# OZ440-SE100-CAR003_sheet15.net
KiCad netlist of a schematic drawn in Altium Designer
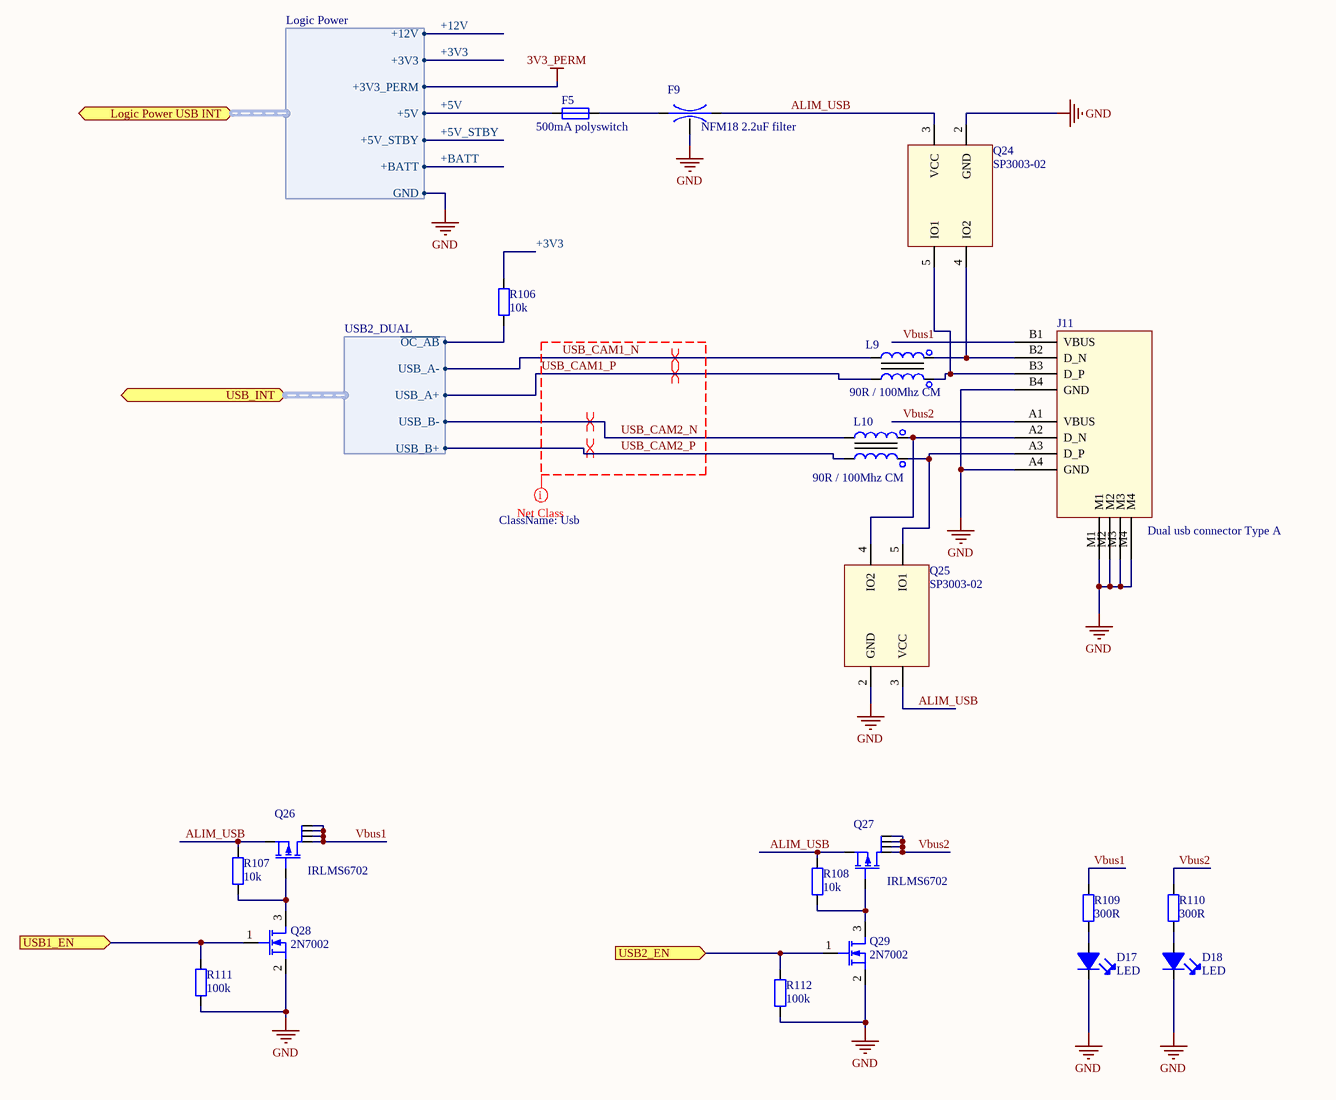
[diagram p0: OZ440-SE100-CAR003_sheet15.SchDoc]

(export (version "E")
  (design (tool "Eeschema 10.0.6"))
  (components
    (comp (ref "D17")
      (value "LED")
      (footprint "0603-SPE-LED")
      (description "SMD Green LED 0603")
      (fields (field (name "DISPLAYED REFERENCE") "LED") (field (name "MANUFACTURER") "KingBright"))
      (libsource (lib "lib_NAIO") (part "LED"))
    )
    (comp (ref "D18")
      (value "LED")
      (footprint "0603-SPE-LED")
      (description "SMD Green LED 0603")
      (fields (field (name "DISPLAYED REFERENCE") "LED") (field (name "MANUFACTURER") "KingBright"))
      (libsource (lib "lib_NAIO") (part "LED"))
    )
    (comp (ref "F5")
      (value "FUSE-SMD")
      (footprint "R0805-STD")
      (description "0805 500mA resettable fuse")
      (fields (field (name "DISPLAYED REFERENCE") "500mA polyswitch") (field (name "MANUFACTURER") "BOURNS"))
      (libsource (lib "lib_NAIO") (part "FUSE-SMD"))
    )
    (comp (ref "F9")
      (value "LC_FILTER-STD")
      (footprint "LC_0603-STD")
      (description "2A LC filter")
      (fields
        (field (name "DISPLAYED REFERENCE") "NFM18 2.2uF filter")
        (field (name "MANUFACTURER") "MURATA")
      )
      (libsource (lib "lib_NAIO") (part "LC_FILTER-STD"))
    )
    (comp (ref "J11")
      (value "CONN-STD_USB_A_DUAL")
      (footprint "CONN-STD-USB_A")
      (description "Dual USB Type A connector")
      (fields
        (field (name "DISPLAYED REFERENCE") "Dual usb connector Type A")
        (field (name "MANUFACTURER") "FCI")
      )
      (libsource (lib "lib_NAIO") (part "CONN-STD_USB_A_DUAL"))
    )
    (comp (ref "L9")
      (value "IND-MC-SMD")
      (footprint "L-SPE-0805_MC_EXC34")
      (description "USB common mode inductor")
      (fields
        (field (name "DISPLAYED REFERENCE") "90R / 100Mhz CM")
        (field (name "MANUFACTURER") "PANASONIC")
      )
      (libsource (lib "lib_NAIO") (part "IND-MC-SMD"))
    )
    (comp (ref "L10")
      (value "IND-MC-SMD")
      (footprint "L-SPE-0805_MC_EXC34")
      (description "USB common mode inductor")
      (fields
        (field (name "DISPLAYED REFERENCE") "90R / 100Mhz CM")
        (field (name "MANUFACTURER") "PANASONIC")
      )
      (libsource (lib "lib_NAIO") (part "IND-MC-SMD"))
    )
    (comp (ref "Q24")
      (value "SP03003_02-SC70")
      (footprint "SC70-SPE-SP3003")
      (description "Low capacitance ESD TVS")
      (fields (field (name "DISPLAYED REFERENCE") "SP3003-02") (field (name "MANUFACTURER") "LITTLEFUSE"))
      (libsource (lib "") (part "SP03003_02-SC70_1"))
    )
    (comp (ref "Q25")
      (value "SP03003_02-SC70")
      (footprint "SC70-SPE-SP3003")
      (description "Low capacitance ESD TVS")
      (fields (field (name "DISPLAYED REFERENCE") "SP3003-02") (field (name "MANUFACTURER") "LITTLEFUSE"))
      (libsource (lib "lib_NAIO") (part "SP03003_02-SC70"))
    )
    (comp (ref "Q26")
      (value "IRLMS6702-MICRO6")
      (footprint "MICRO6-SPE-IRLMS6702")
      (description "2A P channel MOSFET in MICRO6 package")
      (fields (field (name "DISPLAYED REFERENCE") "IRLMS6702") (field (name "MANUFACTURER") "IRF"))
      (libsource (lib "lib_NAIO") (part "IRLMS6702-MICRO6"))
    )
    (comp (ref "Q27")
      (value "IRLMS6702-MICRO6")
      (footprint "MICRO6-SPE-IRLMS6702")
      (description "2A P channel MOSFET in MICRO6 package")
      (fields (field (name "DISPLAYED REFERENCE") "IRLMS6702") (field (name "MANUFACTURER") "IRF"))
      (libsource (lib "lib_NAIO") (part "IRLMS6702-MICRO6"))
    )
    (comp (ref "Q28")
      (value "2N7002-SMD3P")
      (footprint "SOT23-SPE-2N7002")
      (description "N-Channel Enhancement Mode Field Effect Transistor")
      (fields (field (name "DISPLAYED REFERENCE") "2N7002") (field (name "MANUFACTURER") "FAIRCHILD"))
      (libsource (lib "lib_NAIO") (part "2N7002-SMD3P"))
    )
    (comp (ref "Q29")
      (value "2N7002-SMD3P")
      (footprint "SOT23-SPE-2N7002")
      (description "N-Channel Enhancement Mode Field Effect Transistor")
      (fields (field (name "DISPLAYED REFERENCE") "2N7002") (field (name "MANUFACTURER") "FAIRCHILD"))
      (libsource (lib "lib_NAIO") (part "2N7002-SMD3P"))
    )
    (comp (ref "R106")
      (value "RES-SMD")
      (footprint "R0805-STD")
      (description "10k Ohm 0805 SMD resistor")
      (fields
        (field (name "DISPLAYED REFERENCE") "10k")
        (field (name "TOLERANCE") "1 %")
        (field (name "MANUFACTURER") "Vishay")
      )
      (libsource (lib "lib_NAIO") (part "RES-SMD"))
    )
    (comp (ref "R107")
      (value "RES-SMD")
      (footprint "R0805-STD")
      (description "10k Ohm 0805 SMD resistor")
      (fields
        (field (name "DISPLAYED REFERENCE") "10k")
        (field (name "TOLERANCE") "1 %")
        (field (name "MANUFACTURER") "Vishay")
      )
      (libsource (lib "lib_NAIO") (part "RES-SMD"))
    )
    (comp (ref "R108")
      (value "RES-SMD")
      (footprint "R0805-STD")
      (description "10k Ohm 0805 SMD resistor")
      (fields
        (field (name "DISPLAYED REFERENCE") "10k")
        (field (name "TOLERANCE") "1 %")
        (field (name "MANUFACTURER") "Vishay")
      )
      (libsource (lib "lib_NAIO") (part "RES-SMD"))
    )
    (comp (ref "R109")
      (value "RES-SMD")
      (footprint "R0805-STD")
      (description "300 ohm 0805 SMD resistor")
      (fields
        (field (name "DISPLAYED REFERENCE") "300R")
        (field (name "TOLERANCE") "1%")
        (field (name "MANUFACTURER") "Vishay")
      )
      (libsource (lib "lib_NAIO") (part "RES-SMD"))
    )
    (comp (ref "R110")
      (value "RES-SMD")
      (footprint "R0805-STD")
      (description "300 ohm 0805 SMD resistor")
      (fields
        (field (name "DISPLAYED REFERENCE") "300R")
        (field (name "TOLERANCE") "1%")
        (field (name "MANUFACTURER") "Vishay")
      )
      (libsource (lib "lib_NAIO") (part "RES-SMD"))
    )
    (comp (ref "R111")
      (value "RES-SMD")
      (footprint "R0805-STD")
      (description "100k Ohm 0805 SMD resistor")
      (fields
        (field (name "DISPLAYED REFERENCE") "100k")
        (field (name "TOLERANCE") "1 %")
        (field (name "MANUFACTURER") "Vishay")
      )
      (libsource (lib "lib_NAIO") (part "RES-SMD"))
    )
    (comp (ref "R112")
      (value "RES-SMD")
      (footprint "R0805-STD")
      (description "100k Ohm 0805 SMD resistor")
      (fields
        (field (name "DISPLAYED REFERENCE") "100k")
        (field (name "TOLERANCE") "1 %")
        (field (name "MANUFACTURER") "Vishay")
      )
      (libsource (lib "lib_NAIO") (part "RES-SMD"))
    )
  )
  (nets
    (net (code "4") (name "/+3V3") (class "Default")
      (node (ref "R106") (pin "2") (pinfunction "2_2") (pintype "passive"))
    )
    (net (code "5") (name "/+5V") (class "Default")
      (node (ref "F5") (pin "1") (pinfunction "1_1") (pintype "passive"))
    )
    (net (code "9") (name "/ALIM_USB") (class "Default")
      (node (ref "F9") (pin "2") (pinfunction "B_2") (pintype "passive"))
      (node (ref "Q24") (pin "3") (pinfunction "VCC_3") (pintype "passive"))
      (node (ref "Q25") (pin "3") (pinfunction "VCC_3") (pintype "passive"))
      (node (ref "Q26") (pin "4") (pinfunction "S_4") (pintype "passive"))
      (node (ref "Q27") (pin "4") (pinfunction "S_4") (pintype "passive"))
      (node (ref "R107") (pin "2") (pinfunction "2_2") (pintype "passive"))
      (node (ref "R108") (pin "2") (pinfunction "2_2") (pintype "passive"))
    )
    (net (code "10") (name "/USB1_EN") (class "Default")
      (node (ref "Q28") (pin "1") (pinfunction "G_1") (pintype "passive"))
      (node (ref "R111") (pin "2") (pinfunction "2_2") (pintype "passive"))
    )
    (net (code "11") (name "/USB2_EN") (class "Default")
      (node (ref "Q29") (pin "1") (pinfunction "G_1") (pintype "passive"))
      (node (ref "R112") (pin "2") (pinfunction "2_2") (pintype "passive"))
    )
    (net (code "12") (name "/USB_CAM1_N") (class "Default")
      (node (ref "L9") (pin "2") (pinfunction "2_2") (pintype "passive"))
    )
    (net (code "13") (name "/USB_CAM1_P") (class "Default")
      (node (ref "L9") (pin "3") (pinfunction "3_3") (pintype "passive"))
    )
    (net (code "14") (name "/USB_CAM2_N") (class "Default")
      (node (ref "L10") (pin "2") (pinfunction "2_2") (pintype "passive"))
    )
    (net (code "15") (name "/USB_CAM2_P") (class "Default")
      (node (ref "L10") (pin "3") (pinfunction "3_3") (pintype "passive"))
    )
    (net (code "16") (name "/Vbus1") (class "Default")
      (node (ref "J11") (pin "B1") (pinfunction "VBUS_B1") (pintype "passive"))
      (node (ref "Q26") (pin "1") (pinfunction "D_1") (pintype "passive"))
      (node (ref "Q26") (pin "2") (pinfunction "D_2") (pintype "passive"))
      (node (ref "Q26") (pin "5") (pinfunction "D_5") (pintype "passive"))
      (node (ref "Q26") (pin "6") (pinfunction "D_6") (pintype "passive"))
      (node (ref "R109") (pin "2") (pinfunction "2_2") (pintype "passive"))
    )
    (net (code "17") (name "/Vbus2") (class "Default")
      (node (ref "J11") (pin "A1") (pinfunction "VBUS_A1") (pintype "passive"))
      (node (ref "Q27") (pin "1") (pinfunction "D_1") (pintype "passive"))
      (node (ref "Q27") (pin "2") (pinfunction "D_2") (pintype "passive"))
      (node (ref "Q27") (pin "5") (pinfunction "D_5") (pintype "passive"))
      (node (ref "Q27") (pin "6") (pinfunction "D_6") (pintype "passive"))
      (node (ref "R110") (pin "2") (pinfunction "2_2") (pintype "passive"))
    )
    (net (code "20") (name "/~{OC_AB}") (class "Default")
      (node (ref "R106") (pin "1") (pinfunction "1_1") (pintype "passive"))
    )
    (net (code "22") (name "GND") (class "Default")
      (node (ref "D17") (pin "2") (pinfunction "2_2") (pintype "passive"))
      (node (ref "D18") (pin "2") (pinfunction "2_2") (pintype "passive"))
      (node (ref "F9") (pin "3") (pinfunction "G_3") (pintype "passive"))
      (node (ref "J11") (pin "A4") (pinfunction "GND_A4") (pintype "passive"))
      (node (ref "J11") (pin "B4") (pinfunction "GND_B4") (pintype "passive"))
      (node (ref "J11") (pin "M1") (pinfunction "M1_M1") (pintype "passive"))
      (node (ref "J11") (pin "M2") (pinfunction "M2_M2") (pintype "passive"))
      (node (ref "J11") (pin "M3") (pinfunction "M3_M3") (pintype "passive"))
      (node (ref "J11") (pin "M4") (pinfunction "M4_M4") (pintype "passive"))
      (node (ref "Q24") (pin "2") (pinfunction "GND_2") (pintype "passive"))
      (node (ref "Q25") (pin "2") (pinfunction "GND_2") (pintype "passive"))
      (node (ref "Q28") (pin "2") (pinfunction "S_2") (pintype "passive"))
      (node (ref "Q29") (pin "2") (pinfunction "S_2") (pintype "passive"))
      (node (ref "R111") (pin "1") (pinfunction "1_1") (pintype "passive"))
      (node (ref "R112") (pin "1") (pinfunction "1_1") (pintype "passive"))
    )
    (net (code "23") (name "Net-(D17-A)") (class "Default")
      (node (ref "D17") (pin "1") (pinfunction "A_1") (pintype "passive"))
      (node (ref "R109") (pin "1") (pinfunction "1_1") (pintype "passive"))
    )
    (net (code "24") (name "Net-(D18-A)") (class "Default")
      (node (ref "D18") (pin "1") (pinfunction "A_1") (pintype "passive"))
      (node (ref "R110") (pin "1") (pinfunction "1_1") (pintype "passive"))
    )
    (net (code "25") (name "Net-(F9-A)") (class "Default")
      (node (ref "F5") (pin "2") (pinfunction "2_2") (pintype "passive"))
      (node (ref "F9") (pin "1") (pinfunction "A_1") (pintype "passive"))
    )
    (net (code "26") (name "Net-(Q24-IO1)") (class "Default")
      (node (ref "J11") (pin "B3") (pinfunction "D_P_B3") (pintype "passive"))
      (node (ref "L9") (pin "4") (pinfunction "4_4") (pintype "passive"))
      (node (ref "Q24") (pin "5") (pinfunction "IO1_5") (pintype "passive"))
    )
    (net (code "27") (name "Net-(Q24-IO2)") (class "Default")
      (node (ref "J11") (pin "B2") (pinfunction "D_N_B2") (pintype "passive"))
      (node (ref "L9") (pin "1") (pinfunction "1_1") (pintype "passive"))
      (node (ref "Q24") (pin "4") (pinfunction "IO2_4") (pintype "passive"))
    )
    (net (code "28") (name "Net-(Q25-IO1)") (class "Default")
      (node (ref "J11") (pin "A3") (pinfunction "D_P_A3") (pintype "passive"))
      (node (ref "L10") (pin "4") (pinfunction "4_4") (pintype "passive"))
      (node (ref "Q25") (pin "5") (pinfunction "IO1_5") (pintype "passive"))
    )
    (net (code "29") (name "Net-(Q25-IO2)") (class "Default")
      (node (ref "J11") (pin "A2") (pinfunction "D_N_A2") (pintype "passive"))
      (node (ref "L10") (pin "1") (pinfunction "1_1") (pintype "passive"))
      (node (ref "Q25") (pin "4") (pinfunction "IO2_4") (pintype "passive"))
    )
    (net (code "30") (name "Net-(Q26-G)") (class "Default")
      (node (ref "Q26") (pin "3") (pinfunction "G_3") (pintype "passive"))
      (node (ref "Q28") (pin "3") (pinfunction "D_3") (pintype "passive"))
      (node (ref "R107") (pin "1") (pinfunction "1_1") (pintype "passive"))
    )
    (net (code "31") (name "Net-(Q27-G)") (class "Default")
      (node (ref "Q27") (pin "3") (pinfunction "G_3") (pintype "passive"))
      (node (ref "Q29") (pin "3") (pinfunction "D_3") (pintype "passive"))
      (node (ref "R108") (pin "1") (pinfunction "1_1") (pintype "passive"))
    )
  )
)
